# 06_NRF24L01.net
KiCad netlist of a schematic drawn in Altium Designer
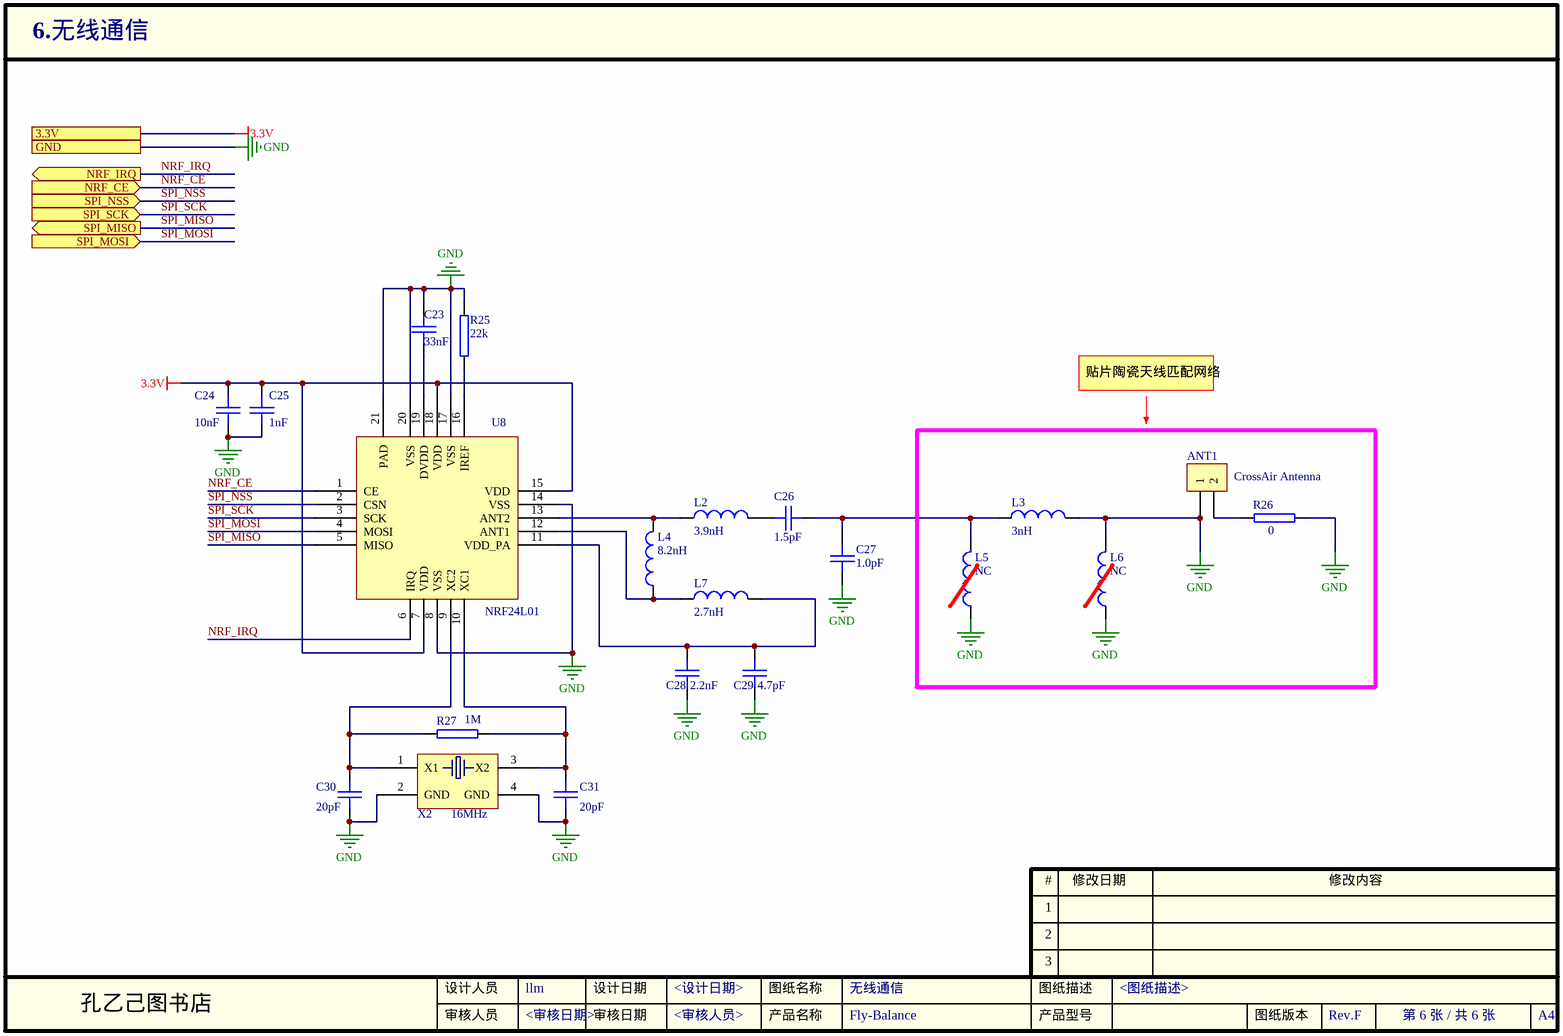
[diagram p0: 06_NRF24L01.SchDoc]

(export (version "E")
  (design (tool "Eeschema 10.0.6"))
  (components
    (comp (ref "ANT1")
      (value "CrossAir Antenna")
      (footprint "ANT-SMD_L3.1-W1.6")
      (description "Connector")
      (libsource (lib "MY_Schlib") (part "CON2"))
    )
    (comp (ref "C23")
      (value "33nF")
      (footprint "0402C")
      (description "电容")
      (libsource (lib "MY_Schlib") (part "CAP"))
    )
    (comp (ref "C24")
      (value "10nF")
      (footprint "0402C")
      (description "电容")
      (libsource (lib "MY_Schlib") (part "CAP"))
    )
    (comp (ref "C25")
      (value "1nF")
      (footprint "0402C")
      (description "电容")
      (libsource (lib "MY_Schlib") (part "CAP"))
    )
    (comp (ref "C26")
      (value "1.5pF")
      (footprint "0402C")
      (description "电容")
      (libsource (lib "MY_Schlib") (part "CAP"))
    )
    (comp (ref "C27")
      (value "1.0pF")
      (footprint "0402C")
      (description "电容")
      (libsource (lib "MY_Schlib") (part "CAP"))
    )
    (comp (ref "C28")
      (value "2.2nF")
      (footprint "0402C")
      (description "电容")
      (libsource (lib "MY_Schlib") (part "CAP"))
    )
    (comp (ref "C29")
      (value "4.7pF")
      (footprint "0402C")
      (description "电容")
      (libsource (lib "MY_Schlib") (part "CAP"))
    )
    (comp (ref "C30")
      (value "20pF")
      (footprint "0402C")
      (description "电容")
      (libsource (lib "MY_Schlib") (part "CAP"))
    )
    (comp (ref "C31")
      (value "20pF")
      (footprint "0402C")
      (description "电容")
      (libsource (lib "MY_Schlib") (part "CAP"))
    )
    (comp (ref "L2")
      (value "3.9nH")
      (footprint "0402R")
      (description "电感")
      (libsource (lib "MY_Schlib") (part "INDUCTOR_1"))
    )
    (comp (ref "L3")
      (value "3nH")
      (footprint "0402R")
      (description "电感")
      (libsource (lib "MY_Schlib") (part "INDUCTOR_1"))
    )
    (comp (ref "L4")
      (value "8.2nH")
      (footprint "0402R")
      (description "电感")
      (libsource (lib "") (part "INDUCTOR_1_1"))
    )
    (comp (ref "L5")
      (value "NC")
      (footprint "0402R")
      (description "电感")
      (libsource (lib "") (part "INDUCTOR_1_1"))
    )
    (comp (ref "L6")
      (value "NC")
      (footprint "0402R")
      (description "电感")
      (libsource (lib "") (part "INDUCTOR_1_1"))
    )
    (comp (ref "L7")
      (value "2.7nH")
      (footprint "0402R")
      (description "电感")
      (libsource (lib "MY_Schlib") (part "INDUCTOR_1"))
    )
    (comp (ref "R25")
      (value "22k")
      (footprint "0402R")
      (description "电阻")
      (libsource (lib "MY_Schlib") (part "RES"))
    )
    (comp (ref "R26")
      (value "0")
      (footprint "0402R")
      (description "电阻")
      (libsource (lib "MY_Schlib") (part "RES"))
    )
    (comp (ref "R27")
      (value "1M")
      (footprint "0402R")
      (description "电阻")
      (libsource (lib "MY_Schlib") (part "RES"))
    )
    (comp (ref "U8")
      (value "NRF24L01")
      (footprint "QFN-20_L4.0-W4.0-P0.50-BL-EP")
      (description "2.4G无线通信芯片")
      (libsource (lib "MY_Schlib") (part "NRF24L01"))
    )
    (comp (ref "X2")
      (value "16MHz")
      (footprint "OSCCC250X320X80-4N")
      (description "4pin贴片无源晶振")
      (libsource (lib "MY_Schlib") (part "XTAL4"))
    )
  )
  (nets
    (net (code "1") (name "/NRF_CE") (class "Default")
      (node (ref "U8") (pin "1") (pinfunction "CE_1") (pintype "passive"))
    )
    (net (code "2") (name "/NRF_IRQ") (class "Default")
      (node (ref "U8") (pin "6") (pinfunction "IRQ_6") (pintype "passive"))
    )
    (net (code "3") (name "/SPI_MISO") (class "Default")
      (node (ref "U8") (pin "5") (pinfunction "MISO_5") (pintype "passive"))
    )
    (net (code "4") (name "/SPI_MOSI") (class "Default")
      (node (ref "U8") (pin "4") (pinfunction "MOSI_4") (pintype "passive"))
    )
    (net (code "5") (name "/SPI_NSS") (class "Default")
      (node (ref "U8") (pin "2") (pinfunction "CSN_2") (pintype "passive"))
    )
    (net (code "6") (name "/SPI_SCK") (class "Default")
      (node (ref "U8") (pin "3") (pinfunction "SCK_3") (pintype "passive"))
    )
    (net (code "7") (name "3.3V") (class "Default")
      (node (ref "C24") (pin "1") (pinfunction "1_1") (pintype "passive"))
      (node (ref "C25") (pin "1") (pinfunction "1_1") (pintype "passive"))
      (node (ref "U8") (pin "15") (pinfunction "VDD_15") (pintype "passive"))
      (node (ref "U8") (pin "18") (pinfunction "VDD_18") (pintype "passive"))
      (node (ref "U8") (pin "7") (pinfunction "VDD_7") (pintype "passive"))
    )
    (net (code "8") (name "GND") (class "Default")
      (node (ref "ANT1") (pin "1") (pinfunction "1_1") (pintype "passive"))
      (node (ref "C23") (pin "1") (pinfunction "1_1") (pintype "passive"))
      (node (ref "C24") (pin "2") (pinfunction "2_2") (pintype "passive"))
      (node (ref "C25") (pin "2") (pinfunction "2_2") (pintype "passive"))
      (node (ref "C27") (pin "1") (pinfunction "1_1") (pintype "passive"))
      (node (ref "C28") (pin "2") (pinfunction "2_2") (pintype "passive"))
      (node (ref "C29") (pin "2") (pinfunction "2_2") (pintype "passive"))
      (node (ref "C30") (pin "1") (pinfunction "1_1") (pintype "passive"))
      (node (ref "C31") (pin "1") (pinfunction "1_1") (pintype "passive"))
      (node (ref "L3") (pin "2") (pinfunction "2_2") (pintype "passive"))
      (node (ref "L5") (pin "1") (pinfunction "1_1") (pintype "passive"))
      (node (ref "L6") (pin "1") (pinfunction "1_1") (pintype "passive"))
      (node (ref "L6") (pin "2") (pinfunction "2_2") (pintype "passive"))
      (node (ref "R25") (pin "1") (pinfunction "1_1") (pintype "passive"))
      (node (ref "R26") (pin "2") (pinfunction "2_2") (pintype "passive"))
      (node (ref "U8") (pin "14") (pinfunction "VSS_14") (pintype "passive"))
      (node (ref "U8") (pin "17") (pinfunction "VSS_17") (pintype "passive"))
      (node (ref "U8") (pin "20") (pinfunction "VSS_20") (pintype "passive"))
      (node (ref "U8") (pin "21") (pinfunction "PAD_21") (pintype "passive"))
      (node (ref "U8") (pin "8") (pinfunction "VSS_8") (pintype "passive"))
      (node (ref "X2") (pin "2") (pinfunction "GND_2") (pintype "passive"))
      (node (ref "X2") (pin "4") (pinfunction "GND_4") (pintype "passive"))
    )
    (net (code "9") (name "Net-(ANT1-Pad2)") (class "Default")
      (node (ref "ANT1") (pin "2") (pinfunction "2_2") (pintype "passive"))
      (node (ref "R26") (pin "1") (pinfunction "1_1") (pintype "passive"))
    )
    (net (code "10") (name "Net-(C26-Pad1)") (class "Default")
      (node (ref "C26") (pin "1") (pinfunction "1_1") (pintype "passive"))
      (node (ref "L2") (pin "2") (pinfunction "2_2") (pintype "passive"))
    )
    (net (code "11") (name "Net-(C26-Pad2)") (class "Default")
      (node (ref "C26") (pin "2") (pinfunction "2_2") (pintype "passive"))
      (node (ref "C27") (pin "2") (pinfunction "2_2") (pintype "passive"))
      (node (ref "L3") (pin "1") (pinfunction "1_1") (pintype "passive"))
      (node (ref "L5") (pin "2") (pinfunction "2_2") (pintype "passive"))
    )
    (net (code "12") (name "Net-(U8-ANT1)") (class "Default")
      (node (ref "L4") (pin "1") (pinfunction "1_1") (pintype "passive"))
      (node (ref "L7") (pin "1") (pinfunction "1_1") (pintype "passive"))
      (node (ref "U8") (pin "12") (pinfunction "ANT1_12") (pintype "passive"))
    )
    (net (code "13") (name "Net-(U8-ANT2)") (class "Default")
      (node (ref "L2") (pin "1") (pinfunction "1_1") (pintype "passive"))
      (node (ref "L4") (pin "2") (pinfunction "2_2") (pintype "passive"))
      (node (ref "U8") (pin "13") (pinfunction "ANT2_13") (pintype "passive"))
    )
    (net (code "14") (name "Net-(U8-DVDD)") (class "Default")
      (node (ref "C23") (pin "2") (pinfunction "2_2") (pintype "passive"))
      (node (ref "U8") (pin "19") (pinfunction "DVDD_19") (pintype "passive"))
    )
    (net (code "15") (name "Net-(U8-IREF)") (class "Default")
      (node (ref "R25") (pin "2") (pinfunction "2_2") (pintype "passive"))
      (node (ref "U8") (pin "16") (pinfunction "IREF_16") (pintype "passive"))
    )
    (net (code "16") (name "Net-(U8-VDD_PA)") (class "Default")
      (node (ref "C28") (pin "1") (pinfunction "1_1") (pintype "passive"))
      (node (ref "C29") (pin "1") (pinfunction "1_1") (pintype "passive"))
      (node (ref "L7") (pin "2") (pinfunction "2_2") (pintype "passive"))
      (node (ref "U8") (pin "11") (pinfunction "VDD_PA_11") (pintype "passive"))
    )
    (net (code "17") (name "Net-(U8-XC1)") (class "Default")
      (node (ref "C31") (pin "2") (pinfunction "2_2") (pintype "passive"))
      (node (ref "R27") (pin "2") (pinfunction "2_2") (pintype "passive"))
      (node (ref "U8") (pin "10") (pinfunction "XC1_10") (pintype "passive"))
      (node (ref "X2") (pin "3") (pinfunction "X2_3") (pintype "passive"))
    )
    (net (code "18") (name "Net-(U8-XC2)") (class "Default")
      (node (ref "C30") (pin "2") (pinfunction "2_2") (pintype "passive"))
      (node (ref "R27") (pin "1") (pinfunction "1_1") (pintype "passive"))
      (node (ref "U8") (pin "9") (pinfunction "XC2_9") (pintype "passive"))
      (node (ref "X2") (pin "1") (pinfunction "X1_1") (pintype "passive"))
    )
  )
)
